# Preamplifier.net
KiCad netlist of a schematic drawn in EAGLE
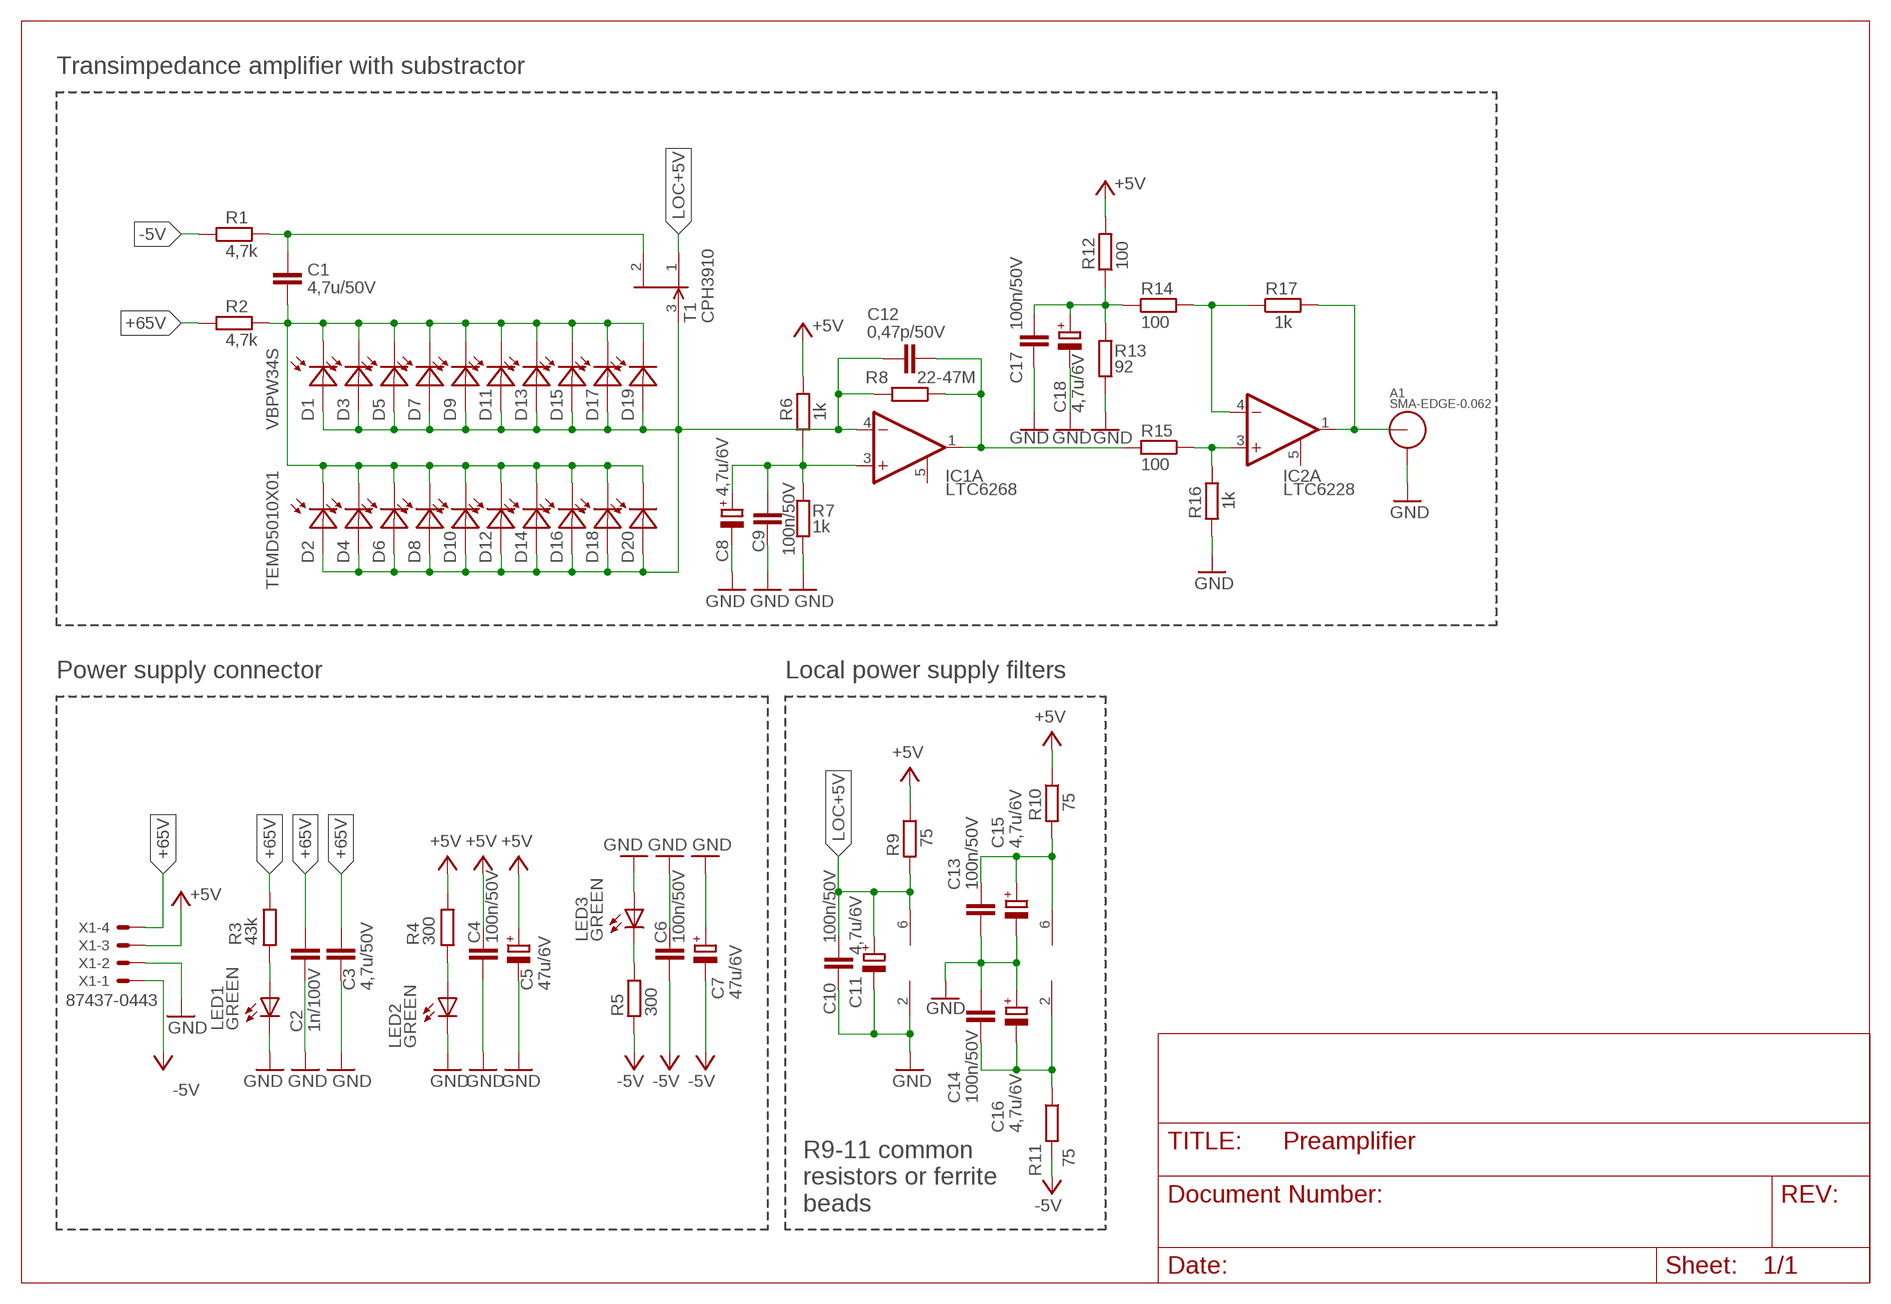
[diagram p0: schematic, sheet 1]

(export (version "E")
  (design (tool "Eeschema 10.0.6"))
  (components
    (comp (ref "A1")
      (value "SMA-EDGE-0.062")
      (footprint "eagle-import:CONSMA003.062")
      (libsource (lib "eagle-import") (part "LINX-SMA-EDGE-0.062"))
    )
    (comp (ref "C1")
      (value "4,7u/50V")
      (footprint "eagle-import:C1206")
      (libsource (lib "eagle-import") (part "C-EUC1206"))
    )
    (comp (ref "C2")
      (value "1n/100V")
      (footprint "eagle-import:C0603")
      (libsource (lib "eagle-import") (part "C-EUC0603"))
    )
    (comp (ref "C3")
      (value "4,7u/50V")
      (footprint "eagle-import:C1206")
      (libsource (lib "eagle-import") (part "rcl_334_C-EUC1206"))
    )
    (comp (ref "C4")
      (value "100n/50V")
      (footprint "eagle-import:C0603")
      (libsource (lib "eagle-import") (part "rcl_334_C-EUC0603"))
    )
    (comp (ref "C5")
      (value "47u/6V")
      (footprint "eagle-import:SMC_B")
      (libsource (lib "eagle-import") (part "CPOL-EUSMCB"))
    )
    (comp (ref "C6")
      (value "100n/50V")
      (footprint "eagle-import:C0603")
      (libsource (lib "eagle-import") (part "rcl_334_C-EUC0603"))
    )
    (comp (ref "C7")
      (value "47u/6V")
      (footprint "eagle-import:SMC_B")
      (libsource (lib "eagle-import") (part "CPOL-EUSMCB"))
    )
    (comp (ref "C8")
      (value "4,7u/6V")
      (footprint "eagle-import:SMC_A")
      (libsource (lib "eagle-import") (part "CPOL-EUSMCA"))
    )
    (comp (ref "C9")
      (value "100n/50V")
      (footprint "eagle-import:C0603")
      (libsource (lib "eagle-import") (part "rcl_334_C-EUC0603"))
    )
    (comp (ref "C10")
      (value "100n/50V")
      (footprint "eagle-import:C0603")
      (libsource (lib "eagle-import") (part "rcl_334_C-EUC0603"))
    )
    (comp (ref "C11")
      (value "4,7u/6V")
      (footprint "eagle-import:SMC_A")
      (libsource (lib "eagle-import") (part "CPOL-EUSMCA"))
    )
    (comp (ref "C12")
      (value "0,47p/50V")
      (footprint "eagle-import:C0603")
      (libsource (lib "eagle-import") (part "rcl_334_C-EUC0603"))
    )
    (comp (ref "C13")
      (value "100n/50V")
      (footprint "eagle-import:C0603")
      (libsource (lib "eagle-import") (part "rcl_334_C-EUC0603"))
    )
    (comp (ref "C14")
      (value "100n/50V")
      (footprint "eagle-import:C0603")
      (libsource (lib "eagle-import") (part "rcl_334_C-EUC0603"))
    )
    (comp (ref "C15")
      (value "4,7u/6V")
      (footprint "eagle-import:SMC_A")
      (libsource (lib "eagle-import") (part "CPOL-EUSMCA"))
    )
    (comp (ref "C16")
      (value "4,7u/6V")
      (footprint "eagle-import:SMC_A")
      (libsource (lib "eagle-import") (part "CPOL-EUSMCA"))
    )
    (comp (ref "C17")
      (value "100n/50V")
      (footprint "eagle-import:C0603")
      (libsource (lib "eagle-import") (part "rcl_334_C-EUC0603"))
    )
    (comp (ref "C18")
      (value "4,7u/6V")
      (footprint "eagle-import:SMC_A")
      (libsource (lib "eagle-import") (part "CPOL-EUSMCA"))
    )
    (comp (ref "D1")
      (value "VBPW34S")
      (footprint "eagle-import:SOD6439X130N")
      (fields (field (name "MF") "Vishay"))
      (libsource (lib "eagle-import") (part "VBPW34S"))
    )
    (comp (ref "D2")
      (value "TEMD5010X01")
      (footprint "eagle-import:DIODE_TEMD5010")
      (libsource (lib "eagle-import") (part "TEMD5010X01"))
    )
    (comp (ref "D3")
      (value "VBPW34S")
      (footprint "eagle-import:SOD6439X130N")
      (fields (field (name "MF") "Vishay"))
      (libsource (lib "eagle-import") (part "VBPW34S"))
    )
    (comp (ref "D4")
      (value "TEMD5010X01")
      (footprint "eagle-import:DIODE_TEMD5010")
      (libsource (lib "eagle-import") (part "TEMD5010X01"))
    )
    (comp (ref "D5")
      (value "VBPW34S")
      (footprint "eagle-import:SOD6439X130N")
      (fields (field (name "MF") "Vishay"))
      (libsource (lib "eagle-import") (part "VBPW34S"))
    )
    (comp (ref "D6")
      (value "TEMD5010X01")
      (footprint "eagle-import:DIODE_TEMD5010")
      (libsource (lib "eagle-import") (part "TEMD5010X01"))
    )
    (comp (ref "D7")
      (value "VBPW34S")
      (footprint "eagle-import:SOD6439X130N")
      (fields (field (name "MF") "Vishay"))
      (libsource (lib "eagle-import") (part "VBPW34S"))
    )
    (comp (ref "D8")
      (value "TEMD5010X01")
      (footprint "eagle-import:DIODE_TEMD5010")
      (libsource (lib "eagle-import") (part "TEMD5010X01"))
    )
    (comp (ref "D9")
      (value "VBPW34S")
      (footprint "eagle-import:SOD6439X130N")
      (fields (field (name "MF") "Vishay"))
      (libsource (lib "eagle-import") (part "VBPW34S"))
    )
    (comp (ref "D10")
      (value "TEMD5010X01")
      (footprint "eagle-import:DIODE_TEMD5010")
      (libsource (lib "eagle-import") (part "TEMD5010X01"))
    )
    (comp (ref "D11")
      (value "VBPW34S")
      (footprint "eagle-import:SOD6439X130N")
      (fields (field (name "MF") "Vishay"))
      (libsource (lib "eagle-import") (part "VBPW34S"))
    )
    (comp (ref "D12")
      (value "TEMD5010X01")
      (footprint "eagle-import:DIODE_TEMD5010")
      (libsource (lib "eagle-import") (part "TEMD5010X01"))
    )
    (comp (ref "D13")
      (value "VBPW34S")
      (footprint "eagle-import:SOD6439X130N")
      (fields (field (name "MF") "Vishay"))
      (libsource (lib "eagle-import") (part "VBPW34S"))
    )
    (comp (ref "D14")
      (value "TEMD5010X01")
      (footprint "eagle-import:DIODE_TEMD5010")
      (libsource (lib "eagle-import") (part "TEMD5010X01"))
    )
    (comp (ref "D15")
      (value "VBPW34S")
      (footprint "eagle-import:SOD6439X130N")
      (fields (field (name "MF") "Vishay"))
      (libsource (lib "eagle-import") (part "VBPW34S"))
    )
    (comp (ref "D16")
      (value "TEMD5010X01")
      (footprint "eagle-import:DIODE_TEMD5010")
      (libsource (lib "eagle-import") (part "TEMD5010X01"))
    )
    (comp (ref "D17")
      (value "VBPW34S")
      (footprint "eagle-import:SOD6439X130N")
      (fields (field (name "MF") "Vishay"))
      (libsource (lib "eagle-import") (part "VBPW34S"))
    )
    (comp (ref "D18")
      (value "TEMD5010X01")
      (footprint "eagle-import:DIODE_TEMD5010")
      (libsource (lib "eagle-import") (part "TEMD5010X01"))
    )
    (comp (ref "D19")
      (value "VBPW34S")
      (footprint "eagle-import:SOD6439X130N")
      (fields (field (name "MF") "Vishay"))
      (libsource (lib "eagle-import") (part "VBPW34S"))
    )
    (comp (ref "D20")
      (value "TEMD5010X01")
      (footprint "eagle-import:DIODE_TEMD5010")
      (libsource (lib "eagle-import") (part "TEMD5010X01"))
    )
    (comp (ref "IC1")
      (value "LTC6268")
      (footprint "eagle-import:TSOT23-6")
      (libsource (lib "eagle-import") (part "LTC6268"))
    )
    (comp (ref "IC2")
      (value "LTC6228")
      (footprint "eagle-import:TSOT23-6")
      (libsource (lib "eagle-import") (part "LTC6268"))
    )
    (comp (ref "LED1")
      (value "GREEN")
      (footprint "eagle-import:CHIPLED_0603")
      (libsource (lib "eagle-import") (part "LEDCHIPLED_0603"))
    )
    (comp (ref "LED2")
      (value "GREEN")
      (footprint "eagle-import:CHIPLED_0603")
      (libsource (lib "eagle-import") (part "LEDCHIPLED_0603"))
    )
    (comp (ref "LED3")
      (value "GREEN")
      (footprint "eagle-import:CHIPLED_0603")
      (libsource (lib "eagle-import") (part "LEDCHIPLED_0603"))
    )
    (comp (ref "R1")
      (value "4,7k")
      (footprint "eagle-import:R0603")
      (libsource (lib "eagle-import") (part "R-EU_R0603"))
    )
    (comp (ref "R2")
      (value "4,7k")
      (footprint "eagle-import:R0603")
      (libsource (lib "eagle-import") (part "R-EU_R0603"))
    )
    (comp (ref "R3")
      (value "43k")
      (footprint "eagle-import:R0603")
      (libsource (lib "eagle-import") (part "R-EU_R0603"))
    )
    (comp (ref "R4")
      (value "300")
      (footprint "eagle-import:R0603")
      (libsource (lib "eagle-import") (part "R-EU_R0603"))
    )
    (comp (ref "R5")
      (value "300")
      (footprint "eagle-import:R0603")
      (libsource (lib "eagle-import") (part "R-EU_R0603"))
    )
    (comp (ref "R6")
      (value "1k")
      (footprint "eagle-import:R0603")
      (libsource (lib "eagle-import") (part "R-EU_R0603"))
    )
    (comp (ref "R7")
      (value "1k")
      (footprint "eagle-import:R0603")
      (libsource (lib "eagle-import") (part "R-EU_R0603"))
    )
    (comp (ref "R8")
      (value "22-47M")
      (footprint "eagle-import:R0603")
      (libsource (lib "eagle-import") (part "R-EU_R0603"))
    )
    (comp (ref "R9")
      (value "75")
      (footprint "eagle-import:R0603")
      (libsource (lib "eagle-import") (part "R-EU_R0603"))
    )
    (comp (ref "R10")
      (value "75")
      (footprint "eagle-import:R0603")
      (libsource (lib "eagle-import") (part "R-EU_R0603"))
    )
    (comp (ref "R11")
      (value "75")
      (footprint "eagle-import:R0603")
      (libsource (lib "eagle-import") (part "R-EU_R0603"))
    )
    (comp (ref "R12")
      (value "100")
      (footprint "eagle-import:R0603")
      (libsource (lib "eagle-import") (part "R-EU_R0603"))
    )
    (comp (ref "R13")
      (value "92")
      (footprint "eagle-import:R0603")
      (libsource (lib "eagle-import") (part "R-EU_R0603"))
    )
    (comp (ref "R14")
      (value "100")
      (footprint "eagle-import:R0603")
      (libsource (lib "eagle-import") (part "R-EU_R0603"))
    )
    (comp (ref "R15")
      (value "100")
      (footprint "eagle-import:R0603")
      (libsource (lib "eagle-import") (part "R-EU_R0603"))
    )
    (comp (ref "R16")
      (value "1k")
      (footprint "eagle-import:R0603")
      (libsource (lib "eagle-import") (part "R-EU_R0603"))
    )
    (comp (ref "R17")
      (value "1k")
      (footprint "eagle-import:R0603")
      (libsource (lib "eagle-import") (part "R-EU_R0603"))
    )
    (comp (ref "T1")
      (value "CPH3910")
      (footprint "eagle-import:SOT23")
      (fields (field (name "MF") "ON Semiconductors"))
      (libsource (lib "eagle-import") (part "CPH3910"))
    )
    (comp (ref "X1")
      (value "87437-0443")
      (footprint "eagle-import:87437-0443")
      (libsource (lib "eagle-import") (part "87438-0487437-0443"))
    )
  )
  (nets
    (net (code "1") (name "+5V") (class "Default")
      (node (ref "C4") (pin "2") (pinfunction "2_2") (pintype "passive"))
      (node (ref "C5") (pin "+") (pinfunction "+_+") (pintype "passive"))
      (node (ref "R10") (pin "1") (pinfunction "1_1") (pintype "passive"))
      (node (ref "R12") (pin "2") (pinfunction "2_2") (pintype "passive"))
      (node (ref "R4") (pin "2") (pinfunction "2_2") (pintype "passive"))
      (node (ref "R6") (pin "2") (pinfunction "2_2") (pintype "passive"))
      (node (ref "R9") (pin "1") (pinfunction "1_1") (pintype "passive"))
      (node (ref "X1") (pin "3") (pinfunction "S_3") (pintype "passive"))
      (node (ref "X1") (pin "7") (pinfunction "S_7") (pintype "passive"))
    )
    (net (code "2") (name "+65V") (class "Default")
      (node (ref "C2") (pin "2") (pinfunction "2_2") (pintype "passive"))
      (node (ref "C3") (pin "1") (pinfunction "1_1") (pintype "passive"))
      (node (ref "R2") (pin "1") (pinfunction "1_1") (pintype "passive"))
      (node (ref "R3") (pin "2") (pinfunction "2_2") (pintype "passive"))
      (node (ref "X1") (pin "4") (pinfunction "S_4") (pintype "passive"))
      (node (ref "X1") (pin "8") (pinfunction "S_8") (pintype "passive"))
    )
    (net (code "3") (name "-5V") (class "Default")
      (node (ref "C6") (pin "1") (pinfunction "1_1") (pintype "passive"))
      (node (ref "C7") (pin "-") (pinfunction "-_-") (pintype "passive"))
      (node (ref "R1") (pin "1") (pinfunction "1_1") (pintype "passive"))
      (node (ref "R11") (pin "2") (pinfunction "2_2") (pintype "passive"))
      (node (ref "R5") (pin "1") (pinfunction "1_1") (pintype "passive"))
      (node (ref "X1") (pin "1") (pinfunction "S_1") (pintype "passive"))
      (node (ref "X1") (pin "5") (pinfunction "S_5") (pintype "passive"))
    )
    (net (code "4") (name "GND") (class "Default")
      (node (ref "A1") (pin "GND1") (pinfunction "P$2_GND1") (pintype "bidirectional"))
      (node (ref "A1") (pin "GND2") (pinfunction "P$2_GND2") (pintype "bidirectional"))
      (node (ref "A1") (pin "GND3") (pinfunction "P$2_GND3") (pintype "bidirectional"))
      (node (ref "A1") (pin "GND4") (pinfunction "P$2_GND4") (pintype "bidirectional"))
      (node (ref "C10") (pin "1") (pinfunction "1_1") (pintype "passive"))
      (node (ref "C11") (pin "-") (pinfunction "-_-") (pintype "passive"))
      (node (ref "C13") (pin "1") (pinfunction "1_1") (pintype "passive"))
      (node (ref "C14") (pin "2") (pinfunction "2_2") (pintype "passive"))
      (node (ref "C15") (pin "-") (pinfunction "-_-") (pintype "passive"))
      (node (ref "C16") (pin "+") (pinfunction "+_+") (pintype "passive"))
      (node (ref "C17") (pin "2") (pinfunction "2_2") (pintype "passive"))
      (node (ref "C18") (pin "-") (pinfunction "-_-") (pintype "passive"))
      (node (ref "C2") (pin "1") (pinfunction "1_1") (pintype "passive"))
      (node (ref "C3") (pin "2") (pinfunction "2_2") (pintype "passive"))
      (node (ref "C4") (pin "1") (pinfunction "1_1") (pintype "passive"))
      (node (ref "C5") (pin "-") (pinfunction "-_-") (pintype "passive"))
      (node (ref "C6") (pin "2") (pinfunction "2_2") (pintype "passive"))
      (node (ref "C7") (pin "+") (pinfunction "+_+") (pintype "passive"))
      (node (ref "C8") (pin "-") (pinfunction "-_-") (pintype "passive"))
      (node (ref "C9") (pin "1") (pinfunction "1_1") (pintype "passive"))
      (node (ref "IC1") (pin "2") (pinfunction "GND_2") (pintype "power_in"))
      (node (ref "LED1") (pin "C") (pinfunction "C_C") (pintype "passive"))
      (node (ref "LED2") (pin "C") (pinfunction "C_C") (pintype "passive"))
      (node (ref "LED3") (pin "A") (pinfunction "A_A") (pintype "passive"))
      (node (ref "R13") (pin "1") (pinfunction "1_1") (pintype "passive"))
      (node (ref "R16") (pin "2") (pinfunction "2_2") (pintype "passive"))
      (node (ref "R7") (pin "1") (pinfunction "1_1") (pintype "passive"))
      (node (ref "X1") (pin "2") (pinfunction "S_2") (pintype "passive"))
      (node (ref "X1") (pin "6") (pinfunction "S_6") (pintype "passive"))
    )
    (net (code "5") (name "LOC+5V") (class "Default")
      (node (ref "C10") (pin "2") (pinfunction "2_2") (pintype "passive"))
      (node (ref "C11") (pin "+") (pinfunction "+_+") (pintype "passive"))
      (node (ref "IC1") (pin "6") (pinfunction "VDD_6") (pintype "power_in"))
      (node (ref "R9") (pin "2") (pinfunction "2_2") (pintype "passive"))
      (node (ref "T1") (pin "1") (pinfunction "S_1") (pintype "passive"))
    )
    (net (code "6") (name "Net-(C17-Pad1)") (class "Default")
      (node (ref "C17") (pin "1") (pinfunction "1_1") (pintype "passive"))
      (node (ref "C18") (pin "+") (pinfunction "+_+") (pintype "passive"))
      (node (ref "R12") (pin "1") (pinfunction "1_1") (pintype "passive"))
      (node (ref "R13") (pin "2") (pinfunction "2_2") (pintype "passive"))
      (node (ref "R14") (pin "1") (pinfunction "1_1") (pintype "passive"))
    )
    (net (code "7") (name "Net-(D10-A)") (class "Default")
      (node (ref "C12") (pin "2") (pinfunction "2_2") (pintype "passive"))
      (node (ref "D1") (pin "A") (pinfunction "A_A") (pintype "passive"))
      (node (ref "D10") (pin "2") (pinfunction "A_2") (pintype "passive"))
      (node (ref "D11") (pin "A") (pinfunction "A_A") (pintype "passive"))
      (node (ref "D12") (pin "2") (pinfunction "A_2") (pintype "passive"))
      (node (ref "D13") (pin "A") (pinfunction "A_A") (pintype "passive"))
      (node (ref "D14") (pin "2") (pinfunction "A_2") (pintype "passive"))
      (node (ref "D15") (pin "A") (pinfunction "A_A") (pintype "passive"))
      (node (ref "D16") (pin "2") (pinfunction "A_2") (pintype "passive"))
      (node (ref "D17") (pin "A") (pinfunction "A_A") (pintype "passive"))
      (node (ref "D18") (pin "2") (pinfunction "A_2") (pintype "passive"))
      (node (ref "D19") (pin "A") (pinfunction "A_A") (pintype "passive"))
      (node (ref "D2") (pin "2") (pinfunction "A_2") (pintype "passive"))
      (node (ref "D20") (pin "2") (pinfunction "A_2") (pintype "passive"))
      (node (ref "D3") (pin "A") (pinfunction "A_A") (pintype "passive"))
      (node (ref "D4") (pin "2") (pinfunction "A_2") (pintype "passive"))
      (node (ref "D5") (pin "A") (pinfunction "A_A") (pintype "passive"))
      (node (ref "D6") (pin "2") (pinfunction "A_2") (pintype "passive"))
      (node (ref "D7") (pin "A") (pinfunction "A_A") (pintype "passive"))
      (node (ref "D8") (pin "2") (pinfunction "A_2") (pintype "passive"))
      (node (ref "D9") (pin "A") (pinfunction "A_A") (pintype "passive"))
      (node (ref "IC1") (pin "4") (pinfunction "-IN_4") (pintype "input"))
      (node (ref "R8") (pin "2") (pinfunction "2_2") (pintype "passive"))
      (node (ref "T1") (pin "3") (pinfunction "G_3") (pintype "passive"))
    )
    (net (code "8") (name "Net-(D10-C)") (class "Default")
      (node (ref "C1") (pin "1") (pinfunction "1_1") (pintype "passive"))
      (node (ref "D1") (pin "C") (pinfunction "C_C") (pintype "passive"))
      (node (ref "D10") (pin "1") (pinfunction "C_1") (pintype "passive"))
      (node (ref "D11") (pin "C") (pinfunction "C_C") (pintype "passive"))
      (node (ref "D12") (pin "1") (pinfunction "C_1") (pintype "passive"))
      (node (ref "D13") (pin "C") (pinfunction "C_C") (pintype "passive"))
      (node (ref "D14") (pin "1") (pinfunction "C_1") (pintype "passive"))
      (node (ref "D15") (pin "C") (pinfunction "C_C") (pintype "passive"))
      (node (ref "D16") (pin "1") (pinfunction "C_1") (pintype "passive"))
      (node (ref "D17") (pin "C") (pinfunction "C_C") (pintype "passive"))
      (node (ref "D18") (pin "1") (pinfunction "C_1") (pintype "passive"))
      (node (ref "D19") (pin "C") (pinfunction "C_C") (pintype "passive"))
      (node (ref "D2") (pin "1") (pinfunction "C_1") (pintype "passive"))
      (node (ref "D20") (pin "1") (pinfunction "C_1") (pintype "passive"))
      (node (ref "D3") (pin "C") (pinfunction "C_C") (pintype "passive"))
      (node (ref "D4") (pin "1") (pinfunction "C_1") (pintype "passive"))
      (node (ref "D5") (pin "C") (pinfunction "C_C") (pintype "passive"))
      (node (ref "D6") (pin "1") (pinfunction "C_1") (pintype "passive"))
      (node (ref "D7") (pin "C") (pinfunction "C_C") (pintype "passive"))
      (node (ref "D8") (pin "1") (pinfunction "C_1") (pintype "passive"))
      (node (ref "D9") (pin "C") (pinfunction "C_C") (pintype "passive"))
      (node (ref "R2") (pin "2") (pinfunction "2_2") (pintype "passive"))
    )
    (net (code "9") (name "Net-(IC1A-+IN)") (class "Default")
      (node (ref "C8") (pin "+") (pinfunction "+_+") (pintype "passive"))
      (node (ref "C9") (pin "2") (pinfunction "2_2") (pintype "passive"))
      (node (ref "IC1") (pin "3") (pinfunction "+IN_3") (pintype "input"))
      (node (ref "R6") (pin "1") (pinfunction "1_1") (pintype "passive"))
      (node (ref "R7") (pin "2") (pinfunction "2_2") (pintype "passive"))
    )
    (net (code "10") (name "Net-(IC1A-OUT)") (class "Default")
      (node (ref "C12") (pin "1") (pinfunction "1_1") (pintype "passive"))
      (node (ref "IC1") (pin "1") (pinfunction "OUT_1") (pintype "output"))
      (node (ref "R15") (pin "2") (pinfunction "2_2") (pintype "passive"))
      (node (ref "R8") (pin "1") (pinfunction "1_1") (pintype "passive"))
    )
    (net (code "11") (name "Net-(IC2A-+IN)") (class "Default")
      (node (ref "IC2") (pin "3") (pinfunction "+IN_3") (pintype "input"))
      (node (ref "R15") (pin "1") (pinfunction "1_1") (pintype "passive"))
      (node (ref "R16") (pin "1") (pinfunction "1_1") (pintype "passive"))
    )
    (net (code "12") (name "Net-(IC2A--IN)") (class "Default")
      (node (ref "IC2") (pin "4") (pinfunction "-IN_4") (pintype "input"))
      (node (ref "R14") (pin "2") (pinfunction "2_2") (pintype "passive"))
      (node (ref "R17") (pin "1") (pinfunction "1_1") (pintype "passive"))
    )
    (net (code "13") (name "Net-(IC2A-OUT)") (class "Default")
      (node (ref "A1") (pin "ANT") (pinfunction "ANT_ANT") (pintype "bidirectional"))
      (node (ref "IC2") (pin "1") (pinfunction "OUT_1") (pintype "output"))
      (node (ref "R17") (pin "2") (pinfunction "2_2") (pintype "passive"))
    )
    (net (code "14") (name "Net-(IC2B-GND)") (class "Default")
      (node (ref "C14") (pin "1") (pinfunction "1_1") (pintype "passive"))
      (node (ref "C16") (pin "-") (pinfunction "-_-") (pintype "passive"))
      (node (ref "IC2") (pin "2") (pinfunction "GND_2") (pintype "power_in"))
      (node (ref "R11") (pin "1") (pinfunction "1_1") (pintype "passive"))
    )
    (net (code "15") (name "Net-(IC2B-VDD)") (class "Default")
      (node (ref "C13") (pin "2") (pinfunction "2_2") (pintype "passive"))
      (node (ref "C15") (pin "+") (pinfunction "+_+") (pintype "passive"))
      (node (ref "IC2") (pin "6") (pinfunction "VDD_6") (pintype "power_in"))
      (node (ref "R10") (pin "2") (pinfunction "2_2") (pintype "passive"))
    )
    (net (code "16") (name "Net-(LED1-PadA)") (class "Default")
      (node (ref "LED1") (pin "A") (pinfunction "A_A") (pintype "passive"))
      (node (ref "R3") (pin "1") (pinfunction "1_1") (pintype "passive"))
    )
    (net (code "17") (name "Net-(LED2-PadA)") (class "Default")
      (node (ref "LED2") (pin "A") (pinfunction "A_A") (pintype "passive"))
      (node (ref "R4") (pin "1") (pinfunction "1_1") (pintype "passive"))
    )
    (net (code "18") (name "Net-(LED3-PadC)") (class "Default")
      (node (ref "LED3") (pin "C") (pinfunction "C_C") (pintype "passive"))
      (node (ref "R5") (pin "2") (pinfunction "2_2") (pintype "passive"))
    )
    (net (code "19") (name "Net-(T1-D)") (class "Default")
      (node (ref "C1") (pin "2") (pinfunction "2_2") (pintype "passive"))
      (node (ref "R1") (pin "2") (pinfunction "2_2") (pintype "passive"))
      (node (ref "T1") (pin "2") (pinfunction "D_2") (pintype "passive"))
    )
    (net (code "20") (name "unconnected-(IC1A-SHDN-Pad5)") (class "Default")
      (node (ref "IC1") (pin "5") (pinfunction "SHDN_5") (pintype "bidirectional"))
    )
    (net (code "21") (name "unconnected-(IC2A-SHDN-Pad5)") (class "Default")
      (node (ref "IC2") (pin "5") (pinfunction "SHDN_5") (pintype "bidirectional"))
    )
  )
)
